# Solar.net
KiCad netlist of a schematic drawn in Altium Designer
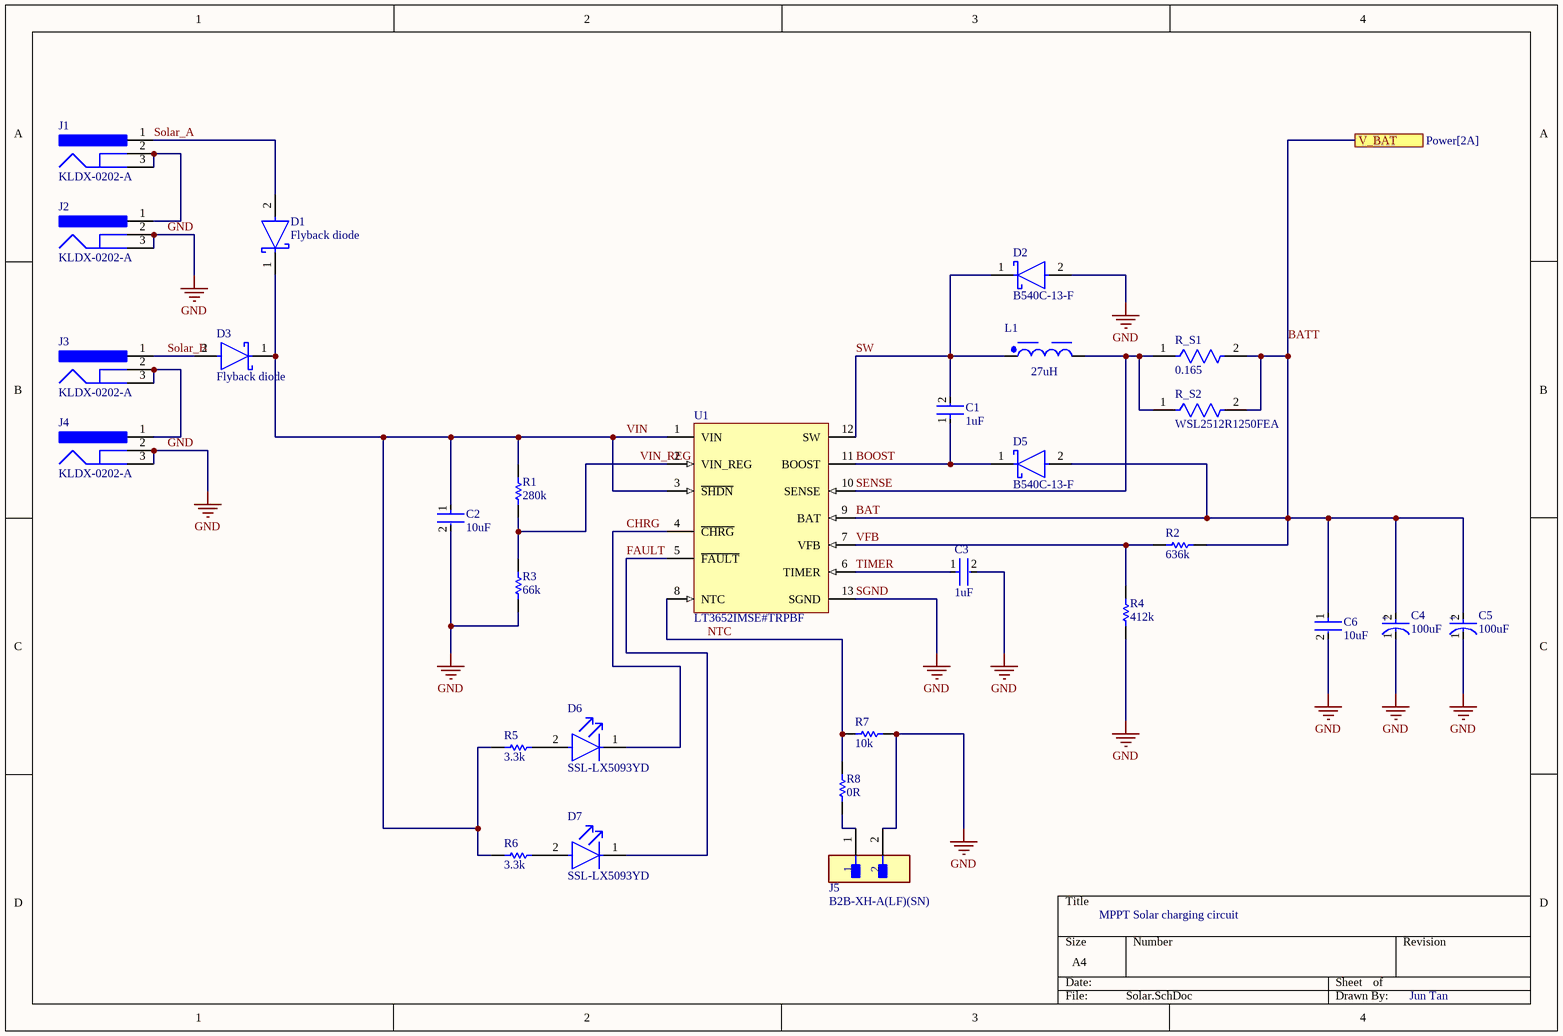
[diagram p0: Solar.SchDoc]

(export (version "E")
  (design (tool "Eeschema 10.0.6"))
  (components
    (comp (ref "C1")
      (value "1uF")
      (footprint "FP-CC1206-1_25-MFG")
      (description "CAP CER 1UF 25V X7R 1206")
      (fields
        (field (name "MANUFACTURER") "Yageo")
        (field (name "MANUFACTURER PART NUMBER") "CC1206MKX7R8BB105")
      )
      (libsource (lib "Altium Content Vault") (part "11868f565c42a9108669ba33697ecf6"))
    )
    (comp (ref "C2")
      (value "10uF")
      (footprint "FP-GRM31C-0_2-e0_3_0_8-MFG")
      (description "Chip Multilayer Ceramic Capacitors for General Purpose, 1206, 10uF, X7R, 15%, 10%, 25V")
      (fields (field (name "TOLERANCE") "10%") (field (name "VOLTAGE") "25V"))
      (libsource (lib "Altium Content Vault") (part "02cd4be3c70576c341d710602a673aa"))
    )
    (comp (ref "C3")
      (value "1uF")
      (footprint "FP-CC1206-1_25-MFG")
      (description "CAP CER 1UF 25V X7R 1206")
      (fields
        (field (name "MANUFACTURER") "Yageo")
        (field (name "MANUFACTURER PART NUMBER") "CC1206MKX7R8BB105")
      )
      (libsource (lib "Altium Content Vault") (part "11868f565c42a9108669ba33697ecf6"))
    )
    (comp (ref "C4")
      (value "100uF")
      (footprint "FP-RAD-TH-D_6_3_0_5-L_11-MFG")
      (description "Aluminum Electrolytic Capacitors (Radial Lead Type) 100uF ±20% 25V")
      (fields (field (name "TOLERANCE") "20%"))
      (libsource (lib "Altium Content Vault") (part "a00bbbee19879c290e62620ae7e47b1"))
    )
    (comp (ref "C5")
      (value "100uF")
      (footprint "FP-RAD-TH-D_6_3_0_5-L_11-MFG")
      (description "Aluminum Electrolytic Capacitors (Radial Lead Type) 100uF ±20% 25V")
      (fields (field (name "TOLERANCE") "20%"))
      (libsource (lib "Altium Content Vault") (part "a00bbbee19879c290e62620ae7e47b1"))
    )
    (comp (ref "C6")
      (value "10uF")
      (footprint "FP-GRM31C-0_2-e0_3_0_8-MFG")
      (description "Chip Multilayer Ceramic Capacitors for General Purpose, 1206, 10uF, X7R, 15%, 10%, 25V")
      (fields (field (name "TOLERANCE") "10%") (field (name "VOLTAGE") "25V"))
      (libsource (lib "Altium Content Vault") (part "02cd4be3c70576c341d710602a673aa"))
    )
    (comp (ref "D1")
      (value "Flyback diode")
      (footprint "FP-DO-201AD-MFG")
      (description "DIODE SCHOTTKY 40V 3A DO201AD")
      (fields
        (field (name "MANUFACTURER PART NUMBER") "1N5822")
        (field (name "OCTOPART") "https://octopart.com/1n5822-stmicroelectronics-323225")
      )
      (libsource (lib "Altium Content Vault") (part "1d6ec82d83fb6aee721767c19dac4b9"))
    )
    (comp (ref "D2")
      (value "B540C-13-F")
      (footprint "FP-SMC-MFG")
      (description "DIODE SCHOTTKY 40V 5A SMC")
      (fields
        (field (name "OCTOPART") "https://octopart.com/b540c-13-f-diodes+inc.-325873")
        (field (name "MANUFACTURER") "Diodes Inc.")
      )
      (libsource (lib "Altium Content Vault") (part "1d6ec82d83fb6aee721767c19dac4b9"))
    )
    (comp (ref "D3")
      (value "Flyback diode")
      (footprint "FP-DO-201AD-MFG")
      (description "DIODE SCHOTTKY 40V 3A DO201AD")
      (fields
        (field (name "MANUFACTURER PART NUMBER") "1N5822")
        (field (name "OCTOPART") "https://octopart.com/1n5822-stmicroelectronics-323225")
      )
      (libsource (lib "Altium Content Vault") (part "1d6ec82d83fb6aee721767c19dac4b9"))
    )
    (comp (ref "D5")
      (value "B540C-13-F")
      (footprint "FP-SMC-MFG")
      (description "DIODE SCHOTTKY 40V 5A SMC")
      (fields
        (field (name "OCTOPART") "https://octopart.com/b540c-13-f-diodes+inc.-325873")
        (field (name "MANUFACTURER") "Diodes Inc.")
      )
      (libsource (lib "Altium Content Vault") (part "1d6ec82d83fb6aee721767c19dac4b9"))
    )
    (comp (ref "D6")
      (value "SSL-LX5093YD")
      (footprint "FP-SSL-LX5093YD-MFG")
      (description "LED YELLOW DIFFUSED T-1 3/4 T/H")
      (libsource (lib "Altium Content Vault") (part "8706943c75ba83719d021d2fdc84c58"))
    )
    (comp (ref "D7")
      (value "SSL-LX5093YD")
      (footprint "FP-SSL-LX5093YD-MFG")
      (description "LED YELLOW DIFFUSED T-1 3/4 T/H")
      (libsource (lib "Altium Content Vault") (part "8706943c75ba83719d021d2fdc84c58"))
    )
    (comp (ref "J1")
      (value "KLDX-0202-A")
      (footprint "KYCN-KLDX-0202-A_V")
      (description "DC Power Jack, 24 V, 3.5 A, -25 to 85 degC, 3-Pin THD, RoHS")
      (fields (field (name "MANUFACTURER") "Kycon"))
      (libsource (lib "Altium Content Vault") (part "JACK-2CD3-RN"))
    )
    (comp (ref "J2")
      (value "KLDX-0202-A")
      (footprint "KYCN-KLDX-0202-A_V")
      (description "DC Power Jack, 24 V, 3.5 A, -25 to 85 degC, 3-Pin THD, RoHS")
      (fields (field (name "MANUFACTURER") "Kycon"))
      (libsource (lib "Altium Content Vault") (part "JACK-2CD3-RN"))
    )
    (comp (ref "J3")
      (value "KLDX-0202-A")
      (footprint "KYCN-KLDX-0202-A_V")
      (description "DC Power Jack, 24 V, 3.5 A, -25 to 85 degC, 3-Pin THD, RoHS")
      (fields (field (name "MANUFACTURER") "Kycon"))
      (libsource (lib "Altium Content Vault") (part "JACK-2CD3-RN"))
    )
    (comp (ref "J4")
      (value "KLDX-0202-A")
      (footprint "KYCN-KLDX-0202-A_V")
      (description "DC Power Jack, 24 V, 3.5 A, -25 to 85 degC, 3-Pin THD, RoHS")
      (fields (field (name "MANUFACTURER") "Kycon"))
      (libsource (lib "Altium Content Vault") (part "JACK-2CD3-RN"))
    )
    (comp (ref "J5")
      (value "B2B-XH-A(LF)(SN)")
      (footprint "FP-B2B-XH-A_LF_SN-MFG")
      (description "CONN HEADER VERT 2POS 2.5MM")
      (libsource (lib "Altium Content Vault") (part "3bc925449376181038e59eaffc5286c"))
    )
    (comp (ref "L1")
      (value "27uH")
      (footprint "WE-PD_7345R")
      (description "WE-PD Robust SMT Shielded Power Inductor")
      (fields (field (name "TOLERANCE") "20%"))
      (libsource (lib "Altium Content Vault") (part "Inductor - 2"))
    )
    (comp (ref "R1")
      (value "280k")
      (footprint "RESA60-630X240")
      (description "Axial Resistor, 100 Ohm, +/- 1%, 0.25 W, -55 to 155 degC, 2-Pin THD, RoHS, Bulk")
      (fields (field (name "TOLERANCE") "1%"))
      (libsource (lib "Altium Content Vault") (part "RES-2"))
    )
    (comp (ref "R2")
      (value "636k")
      (footprint "RESA60-630X240")
      (description "Axial Resistor, 100 Ohm, +/- 1%, 0.25 W, -55 to 155 degC, 2-Pin THD, RoHS, Bulk")
      (fields (field (name "TOLERANCE") "1%"))
      (libsource (lib "Altium Content Vault") (part "RES-2"))
    )
    (comp (ref "R3")
      (value "66k")
      (footprint "RESA60-630X240")
      (description "Axial Resistor, 100 Ohm, +/- 1%, 0.25 W, -55 to 155 degC, 2-Pin THD, RoHS, Bulk")
      (fields (field (name "TOLERANCE") "1%"))
      (libsource (lib "Altium Content Vault") (part "RES-2"))
    )
    (comp (ref "R4")
      (value "412k")
      (footprint "RESA60-630X240")
      (description "Axial Resistor, 100 Ohm, +/- 1%, 0.25 W, -55 to 155 degC, 2-Pin THD, RoHS, Bulk")
      (fields (field (name "TOLERANCE") "1%"))
      (libsource (lib "Altium Content Vault") (part "RES-2"))
    )
    (comp (ref "R5")
      (value "3.3k")
      (footprint "RESA60-630X240")
      (description "Axial Resistor, 100 Ohm, +/- 1%, 0.25 W, -55 to 155 degC, 2-Pin THD, RoHS, Bulk")
      (fields (field (name "TOLERANCE") "1%"))
      (libsource (lib "Altium Content Vault") (part "RES-2"))
    )
    (comp (ref "R6")
      (value "3.3k")
      (footprint "RESA60-630X240")
      (description "Axial Resistor, 100 Ohm, +/- 1%, 0.25 W, -55 to 155 degC, 2-Pin THD, RoHS, Bulk")
      (fields (field (name "TOLERANCE") "1%"))
      (libsource (lib "Altium Content Vault") (part "RES-2"))
    )
    (comp (ref "R7")
      (value "10k")
      (footprint "RESA60-630X240")
      (description "Axial Resistor, 100 Ohm, +/- 1%, 0.25 W, -55 to 155 degC, 2-Pin THD, RoHS, Bulk")
      (fields (field (name "TOLERANCE") "1%"))
      (libsource (lib "Altium Content Vault") (part "RES-2"))
    )
    (comp (ref "R8")
      (value "0R")
      (footprint "RESA60-630X240")
      (description "Axial Resistor, 100 Ohm, +/- 1%, 0.25 W, -55 to 155 degC, 2-Pin THD, RoHS, Bulk")
      (fields (field (name "TOLERANCE") "1%"))
      (libsource (lib "Altium Content Vault") (part "RES-2"))
    )
    (comp (ref "R_S1")
      (value "0.165")
      (footprint "FP-WSL2512-MFG")
      (description "Res Metal Strip 2512 0.125 Ohm 1% 1W ±75ppm/°C Molded SMD SMD Embossed Plastic T/R")
      (fields (field (name "TOLERANCE") "1%"))
      (libsource (lib "Altium Content Vault") (part "1029c3af85768c4190bb7ad29bc67b5"))
    )
    (comp (ref "R_S2")
      (value "WSL2512R1250FEA")
      (footprint "FP-WSL2512-MFG")
      (description "Res Metal Strip 2512 0.125 Ohm 1% 1W ±75ppm/°C Molded SMD SMD Embossed Plastic T/R")
      (fields (field (name "TOLERANCE") "1%"))
      (libsource (lib "Altium Content Vault") (part "1029c3af85768c4190bb7ad29bc67b5"))
    )
    (comp (ref "U1")
      (value "LT3652IMSE#TRPBF")
      (footprint "LT-MSE-12-EDP_L")
      (fields (field (name "MANUFACTURER") "Linear Technology"))
      (libsource (lib "Altium Content Vault") (part "LT-LT3652-MSE-12_3652HV-DD-12"))
    )
  )
  (nets
    (net (code "1") (name "/BAT") (class "Default")
      (node (ref "C4") (pin "2") (pinfunction "A_2") (pintype "passive"))
      (node (ref "C5") (pin "2") (pinfunction "A_2") (pintype "passive"))
      (node (ref "C6") (pin "1") (pinfunction "1_1") (pintype "passive"))
      (node (ref "D5") (pin "2") (pinfunction "A_2") (pintype "passive"))
      (node (ref "R2") (pin "1") (pinfunction "1_1") (pintype "passive"))
      (node (ref "R_S1") (pin "2") (pinfunction "2_2") (pintype "passive"))
      (node (ref "R_S2") (pin "2") (pinfunction "2_2") (pintype "passive"))
      (node (ref "U1") (pin "9") (pinfunction "BAT_9") (pintype "input"))
    )
    (net (code "2") (name "/BOOST") (class "Default")
      (node (ref "C1") (pin "1") (pinfunction "1_1") (pintype "passive"))
      (node (ref "D5") (pin "1") (pinfunction "C_1") (pintype "passive"))
      (node (ref "U1") (pin "11") (pinfunction "BOOST_11") (pintype "power_in"))
    )
    (net (code "3") (name "/CHRG") (class "Default")
      (node (ref "D6") (pin "1") (pinfunction "C_1") (pintype "passive"))
      (node (ref "U1") (pin "4") (pinfunction "~{CHRG}_4") (pintype "tri_state"))
    )
    (net (code "4") (name "/FAULT") (class "Default")
      (node (ref "D7") (pin "1") (pinfunction "C_1") (pintype "passive"))
      (node (ref "U1") (pin "5") (pinfunction "~{FAULT}_5") (pintype "tri_state"))
    )
    (net (code "5") (name "/NTC") (class "Default")
      (node (ref "R7") (pin "2") (pinfunction "2_2") (pintype "passive"))
      (node (ref "R8") (pin "2") (pinfunction "2_2") (pintype "passive"))
      (node (ref "U1") (pin "8") (pinfunction "NTC_8") (pintype "input"))
    )
    (net (code "6") (name "/SENSE") (class "Default")
      (node (ref "L1") (pin "2") (pinfunction "2_2") (pintype "passive"))
      (node (ref "R_S1") (pin "1") (pinfunction "1_1") (pintype "passive"))
      (node (ref "R_S2") (pin "1") (pinfunction "1_1") (pintype "passive"))
      (node (ref "U1") (pin "10") (pinfunction "SENSE_10") (pintype "input"))
    )
    (net (code "7") (name "/SW") (class "Default")
      (node (ref "C1") (pin "2") (pinfunction "2_2") (pintype "passive"))
      (node (ref "D2") (pin "1") (pinfunction "C_1") (pintype "passive"))
      (node (ref "L1") (pin "1") (pinfunction "1_1") (pintype "passive"))
      (node (ref "U1") (pin "12") (pinfunction "SW_12") (pintype "power_in"))
    )
    (net (code "8") (name "/Solar_A") (class "Default")
      (node (ref "D1") (pin "2") (pinfunction "A_2") (pintype "passive"))
      (node (ref "J1") (pin "1") (pinfunction "1_1") (pintype "passive"))
    )
    (net (code "9") (name "/Solar_B") (class "Default")
      (node (ref "D3") (pin "2") (pinfunction "A_2") (pintype "passive"))
      (node (ref "J3") (pin "1") (pinfunction "1_1") (pintype "passive"))
    )
    (net (code "10") (name "/TIMER") (class "Default")
      (node (ref "C3") (pin "1") (pinfunction "1_1") (pintype "passive"))
      (node (ref "U1") (pin "6") (pinfunction "TIMER_6") (pintype "input"))
    )
    (net (code "11") (name "/VFB") (class "Default")
      (node (ref "R2") (pin "2") (pinfunction "2_2") (pintype "passive"))
      (node (ref "R4") (pin "2") (pinfunction "2_2") (pintype "passive"))
      (node (ref "U1") (pin "7") (pinfunction "VFB_7") (pintype "input"))
    )
    (net (code "12") (name "/VIN") (class "Default")
      (node (ref "C2") (pin "1") (pinfunction "1_1") (pintype "passive"))
      (node (ref "D1") (pin "1") (pinfunction "C_1") (pintype "passive"))
      (node (ref "D3") (pin "1") (pinfunction "C_1") (pintype "passive"))
      (node (ref "R1") (pin "2") (pinfunction "2_2") (pintype "passive"))
      (node (ref "R5") (pin "2") (pinfunction "2_2") (pintype "passive"))
      (node (ref "R6") (pin "2") (pinfunction "2_2") (pintype "passive"))
      (node (ref "U1") (pin "1") (pinfunction "VIN_1") (pintype "power_in"))
      (node (ref "U1") (pin "3") (pinfunction "~{SHDN}_3") (pintype "input"))
    )
    (net (code "13") (name "/VIN_REG") (class "Default")
      (node (ref "R1") (pin "1") (pinfunction "1_1") (pintype "passive"))
      (node (ref "R3") (pin "2") (pinfunction "2_2") (pintype "passive"))
      (node (ref "U1") (pin "2") (pinfunction "VIN_REG_2") (pintype "input"))
    )
    (net (code "14") (name "GND") (class "Default")
      (node (ref "C2") (pin "2") (pinfunction "2_2") (pintype "passive"))
      (node (ref "C3") (pin "2") (pinfunction "2_2") (pintype "passive"))
      (node (ref "C4") (pin "1") (pinfunction "C_1") (pintype "passive"))
      (node (ref "C5") (pin "1") (pinfunction "C_1") (pintype "passive"))
      (node (ref "C6") (pin "2") (pinfunction "2_2") (pintype "passive"))
      (node (ref "D2") (pin "2") (pinfunction "A_2") (pintype "passive"))
      (node (ref "J2") (pin "2") (pinfunction "2_2") (pintype "passive"))
      (node (ref "J2") (pin "3") (pinfunction "3_3") (pintype "passive"))
      (node (ref "J4") (pin "2") (pinfunction "2_2") (pintype "passive"))
      (node (ref "J4") (pin "3") (pinfunction "3_3") (pintype "passive"))
      (node (ref "J5") (pin "2") (pinfunction "2_2") (pintype "passive"))
      (node (ref "R3") (pin "1") (pinfunction "1_1") (pintype "passive"))
      (node (ref "R4") (pin "1") (pinfunction "1_1") (pintype "passive"))
      (node (ref "R7") (pin "1") (pinfunction "1_1") (pintype "passive"))
      (node (ref "U1") (pin "13") (pinfunction "SGND_13") (pintype "power_in"))
    )
    (net (code "15") (name "Net-(D6-A)") (class "Default")
      (node (ref "D6") (pin "2") (pinfunction "A_2") (pintype "passive"))
      (node (ref "R5") (pin "1") (pinfunction "1_1") (pintype "passive"))
    )
    (net (code "16") (name "Net-(D7-A)") (class "Default")
      (node (ref "D7") (pin "2") (pinfunction "A_2") (pintype "passive"))
      (node (ref "R6") (pin "1") (pinfunction "1_1") (pintype "passive"))
    )
    (net (code "17") (name "Net-(J1-Pad2)") (class "Default")
      (node (ref "J1") (pin "2") (pinfunction "2_2") (pintype "passive"))
      (node (ref "J1") (pin "3") (pinfunction "3_3") (pintype "passive"))
      (node (ref "J2") (pin "1") (pinfunction "1_1") (pintype "passive"))
    )
    (net (code "18") (name "Net-(J3-Pad2)") (class "Default")
      (node (ref "J3") (pin "2") (pinfunction "2_2") (pintype "passive"))
      (node (ref "J3") (pin "3") (pinfunction "3_3") (pintype "passive"))
      (node (ref "J4") (pin "1") (pinfunction "1_1") (pintype "passive"))
    )
    (net (code "19") (name "Net-(J5-Pad1)") (class "Default")
      (node (ref "J5") (pin "1") (pinfunction "1_1") (pintype "passive"))
      (node (ref "R8") (pin "1") (pinfunction "1_1") (pintype "passive"))
    )
  )
)
